# guest_room_controller_V2.net
KiCad netlist of a schematic drawn in EAGLE
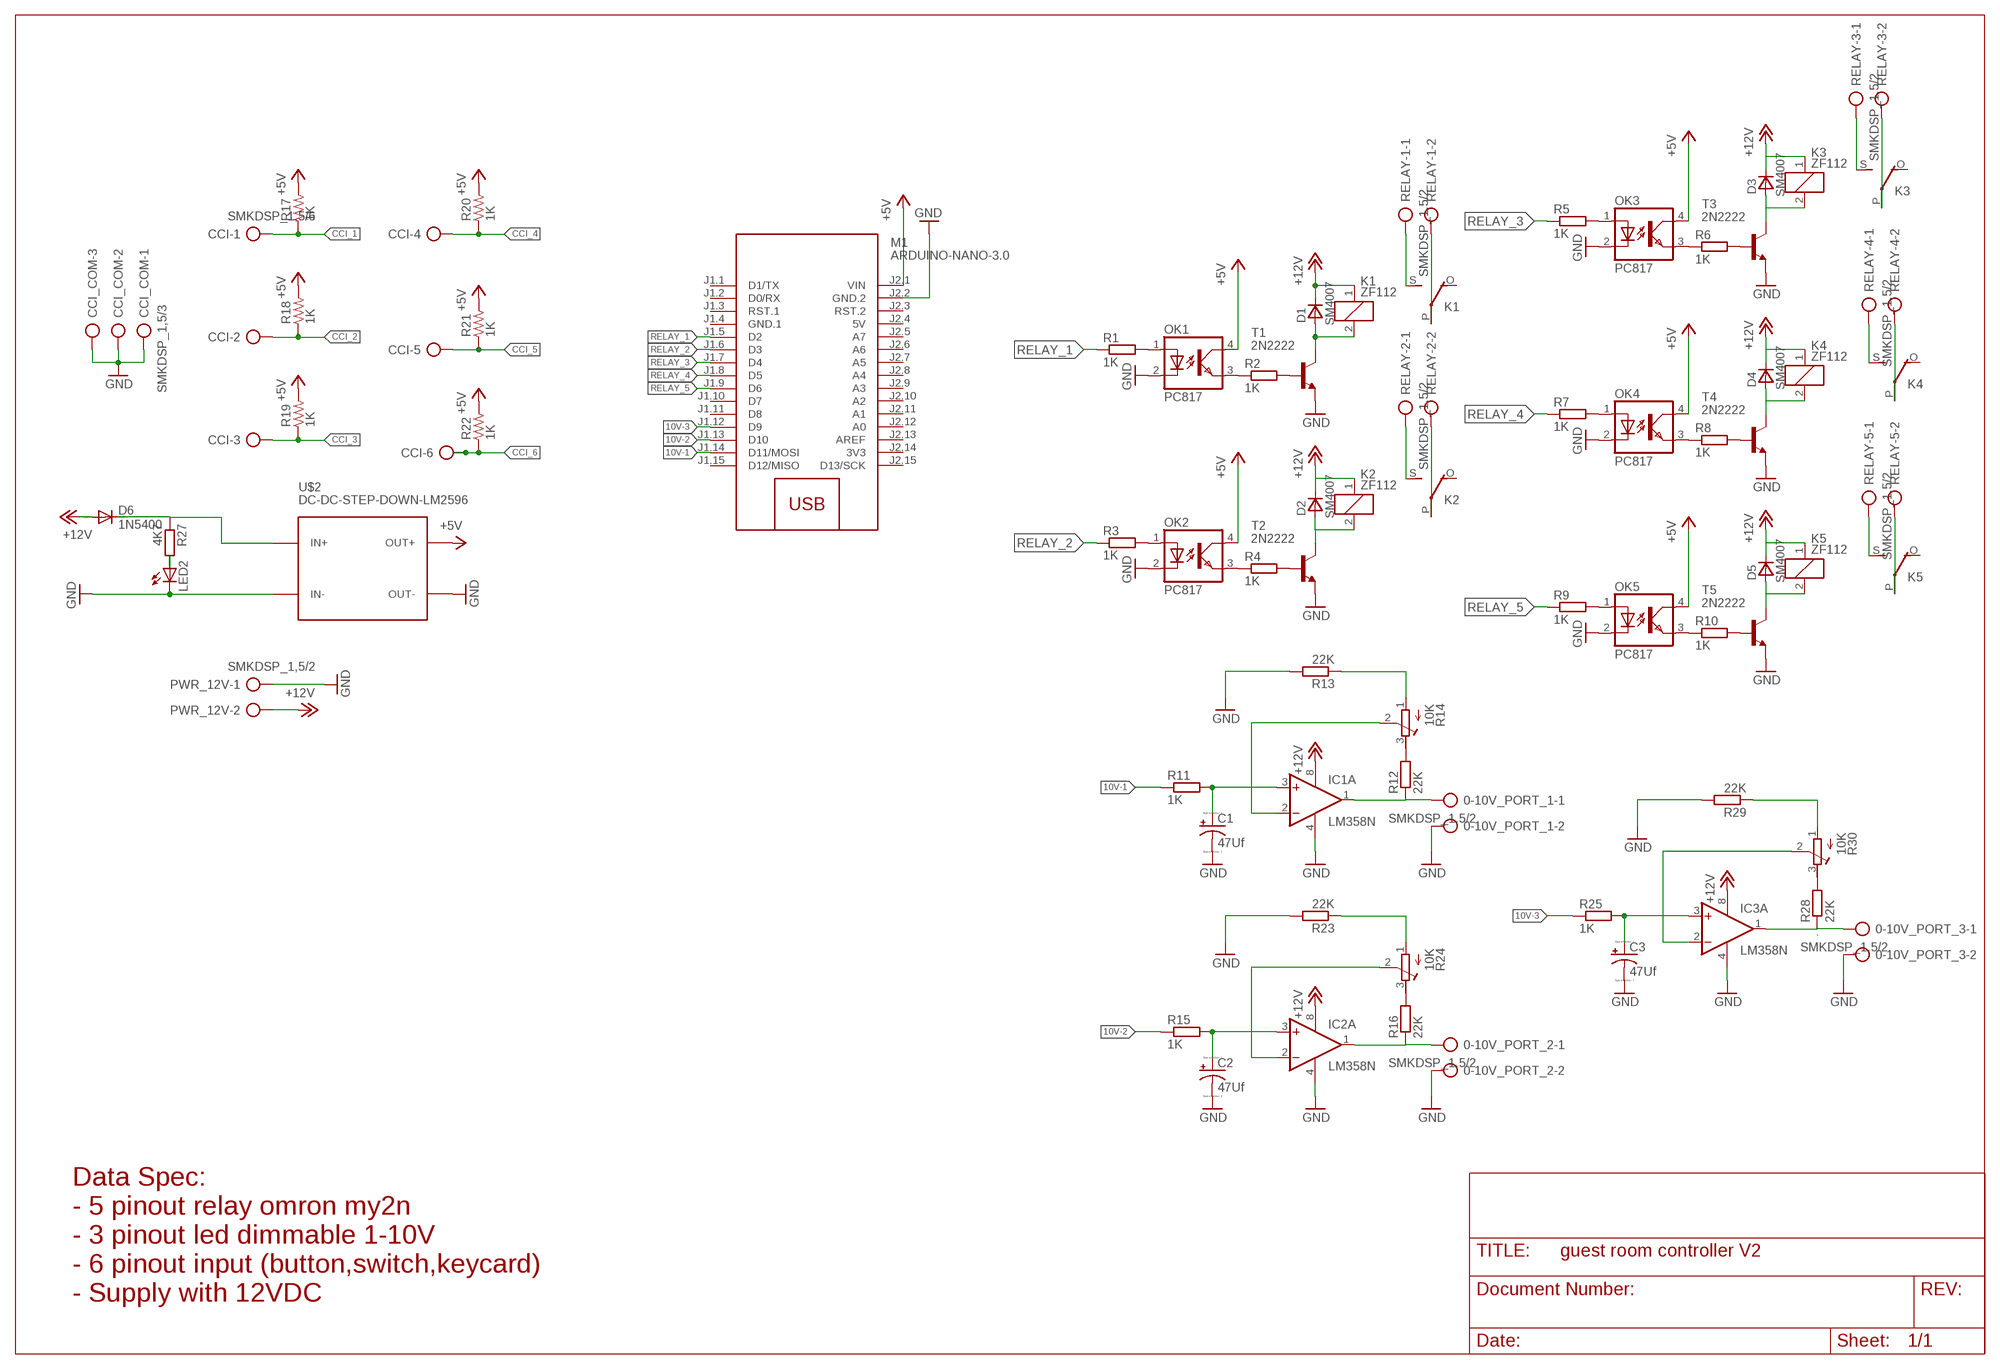
[diagram p0: schematic, sheet 1]

(export (version "E")
  (design (tool "Eeschema 10.0.6"))
  (components
    (comp (ref "0-10V_PORT_1")
      (value "SMKDSP_1,5/2")
      (footprint "eagle-import:SMKDSP_1,5_2")
      (fields (field (name "MF") "FARNELL") (field (name "MPN") "1733570"))
      (libsource (lib "eagle-import") (part "SMKDSP_1,5/2"))
    )
    (comp (ref "0-10V_PORT_2")
      (value "SMKDSP_1,5/2")
      (footprint "eagle-import:SMKDSP_1,5_2")
      (fields (field (name "MF") "FARNELL") (field (name "MPN") "1733570"))
      (libsource (lib "eagle-import") (part "SMKDSP_1,5/2"))
    )
    (comp (ref "0-10V_PORT_3")
      (value "SMKDSP_1,5/2")
      (footprint "eagle-import:SMKDSP_1,5_2")
      (fields (field (name "MF") "FARNELL") (field (name "MPN") "1733570"))
      (libsource (lib "eagle-import") (part "SMKDSP_1,5/2"))
    )
    (comp (ref "C1")
      (value "47Uf")
      (footprint "eagle-import:E2,5-6")
      (libsource (lib "eagle-import") (part "CPOL-USE2.5-6"))
    )
    (comp (ref "C2")
      (value "47Uf")
      (footprint "eagle-import:E2,5-6")
      (libsource (lib "eagle-import") (part "CPOL-USE2.5-6"))
    )
    (comp (ref "C3")
      (value "47Uf")
      (footprint "eagle-import:E2,5-6")
      (libsource (lib "eagle-import") (part "CPOL-USE2.5-6"))
    )
    (comp (ref "CCI")
      (value "SMKDSP_1,5/6")
      (footprint "eagle-import:SMKDSP_1,5_6")
      (fields (field (name "MF") "FARNELL") (field (name "MPN") "1733619"))
      (libsource (lib "eagle-import") (part "SMKDSP_1,5/6"))
    )
    (comp (ref "CCI_COM")
      (value "SMKDSP_1,5/3")
      (footprint "eagle-import:SMKDSP_1,5_3")
      (fields (field (name "MF") "FARNELL") (field (name "MPN") "1733583"))
      (libsource (lib "eagle-import") (part "SMKDSP_1,5/3"))
    )
    (comp (ref "D1")
      (value "SM4007")
      (footprint "eagle-import:MELF-MLL41")
      (libsource (lib "eagle-import") (part "SM4007"))
    )
    (comp (ref "D2")
      (value "SM4007")
      (footprint "eagle-import:MELF-MLL41")
      (libsource (lib "eagle-import") (part "SM4007"))
    )
    (comp (ref "D3")
      (value "SM4007")
      (footprint "eagle-import:MELF-MLL41")
      (libsource (lib "eagle-import") (part "SM4007"))
    )
    (comp (ref "D4")
      (value "SM4007")
      (footprint "eagle-import:MELF-MLL41")
      (libsource (lib "eagle-import") (part "SM4007"))
    )
    (comp (ref "D5")
      (value "SM4007")
      (footprint "eagle-import:MELF-MLL41")
      (libsource (lib "eagle-import") (part "SM4007"))
    )
    (comp (ref "D6")
      (value "1N5400")
      (footprint "eagle-import:DO201-15")
      (libsource (lib "eagle-import") (part "1N5400"))
    )
    (comp (ref "IC1")
      (value "LM358N")
      (footprint "eagle-import:DIL08")
      (libsource (lib "eagle-import") (part "LM358N"))
    )
    (comp (ref "IC2")
      (value "LM358N")
      (footprint "eagle-import:DIL08")
      (libsource (lib "eagle-import") (part "LM358N"))
    )
    (comp (ref "IC3")
      (value "LM358N")
      (footprint "eagle-import:DIL08")
      (libsource (lib "eagle-import") (part "LM358N"))
    )
    (comp (ref "K1")
      (value "ZF112")
      (footprint "eagle-import:ZF112")
      (libsource (lib "eagle-import") (part "ZF112"))
    )
    (comp (ref "K2")
      (value "ZF112")
      (footprint "eagle-import:ZF112")
      (libsource (lib "eagle-import") (part "ZF112"))
    )
    (comp (ref "K3")
      (value "ZF112")
      (footprint "eagle-import:ZF112")
      (libsource (lib "eagle-import") (part "ZF112"))
    )
    (comp (ref "K4")
      (value "ZF112")
      (footprint "eagle-import:ZF112")
      (libsource (lib "eagle-import") (part "ZF112"))
    )
    (comp (ref "K5")
      (value "ZF112")
      (footprint "eagle-import:ZF112")
      (libsource (lib "eagle-import") (part "ZF112"))
    )
    (comp (ref "LED2")
      (value "LED3MM")
      (footprint "eagle-import:LED3MM")
      (libsource (lib "eagle-import") (part "LED3MM"))
    )
    (comp (ref "M1")
      (value "ARDUINO-NANO-3.0")
      (footprint "eagle-import:ARDUINO-NANO-3.0")
      (libsource (lib "eagle-import") (part "ARDUINO-NANO-3.0"))
    )
    (comp (ref "OK1")
      (value "PC817")
      (footprint "eagle-import:DIL04")
      (fields (field (name "MPN") "PC817X4J000F"))
      (libsource (lib "eagle-import") (part "PC817"))
    )
    (comp (ref "OK2")
      (value "PC817")
      (footprint "eagle-import:DIL04")
      (fields (field (name "MPN") "PC817X4J000F"))
      (libsource (lib "eagle-import") (part "PC817"))
    )
    (comp (ref "OK3")
      (value "PC817")
      (footprint "eagle-import:DIL04")
      (fields (field (name "MPN") "PC817X4J000F"))
      (libsource (lib "eagle-import") (part "PC817"))
    )
    (comp (ref "OK4")
      (value "PC817")
      (footprint "eagle-import:DIL04")
      (fields (field (name "MPN") "PC817X4J000F"))
      (libsource (lib "eagle-import") (part "PC817"))
    )
    (comp (ref "OK5")
      (value "PC817")
      (footprint "eagle-import:DIL04")
      (fields (field (name "MPN") "PC817X4J000F"))
      (libsource (lib "eagle-import") (part "PC817"))
    )
    (comp (ref "PWR_12V")
      (value "SMKDSP_1,5/2")
      (footprint "eagle-import:SMKDSP_1,5_2")
      (fields (field (name "MF") "FARNELL") (field (name "MPN") "1733570"))
      (libsource (lib "eagle-import") (part "SMKDSP_1,5/2"))
    )
    (comp (ref "R1")
      (value "1K")
      (footprint "eagle-import:0207_10")
      (libsource (lib "eagle-import") (part "R-EU_0207/10"))
    )
    (comp (ref "R2")
      (value "1K")
      (footprint "eagle-import:0207_10")
      (libsource (lib "eagle-import") (part "R-EU_0207/10"))
    )
    (comp (ref "R3")
      (value "1K")
      (footprint "eagle-import:0207_10")
      (libsource (lib "eagle-import") (part "R-EU_0207/10"))
    )
    (comp (ref "R4")
      (value "1K")
      (footprint "eagle-import:0207_10")
      (libsource (lib "eagle-import") (part "R-EU_0207/10"))
    )
    (comp (ref "R5")
      (value "1K")
      (footprint "eagle-import:0207_10")
      (libsource (lib "eagle-import") (part "R-EU_0207/10"))
    )
    (comp (ref "R6")
      (value "1K")
      (footprint "eagle-import:0207_10")
      (libsource (lib "eagle-import") (part "R-EU_0207/10"))
    )
    (comp (ref "R7")
      (value "1K")
      (footprint "eagle-import:0207_10")
      (libsource (lib "eagle-import") (part "R-EU_0207/10"))
    )
    (comp (ref "R8")
      (value "1K")
      (footprint "eagle-import:0207_10")
      (libsource (lib "eagle-import") (part "R-EU_0207/10"))
    )
    (comp (ref "R9")
      (value "1K")
      (footprint "eagle-import:0207_10")
      (libsource (lib "eagle-import") (part "R-EU_0207/10"))
    )
    (comp (ref "R10")
      (value "1K")
      (footprint "eagle-import:0207_10")
      (libsource (lib "eagle-import") (part "R-EU_0207/10"))
    )
    (comp (ref "R11")
      (value "1K")
      (footprint "eagle-import:0207_10")
      (libsource (lib "eagle-import") (part "R-EU_0207/10"))
    )
    (comp (ref "R12")
      (value "22K")
      (footprint "eagle-import:0207_10")
      (libsource (lib "eagle-import") (part "R-EU_0207/10"))
    )
    (comp (ref "R13")
      (value "22K")
      (footprint "eagle-import:0207_10")
      (libsource (lib "eagle-import") (part "R-EU_0207/10"))
    )
    (comp (ref "R14")
      (value "10K")
      (footprint "eagle-import:RTRIM64P")
      (libsource (lib "eagle-import") (part "R-TRIMM64P"))
    )
    (comp (ref "R15")
      (value "1K")
      (footprint "eagle-import:0207_10")
      (libsource (lib "eagle-import") (part "R-EU_0207/10"))
    )
    (comp (ref "R16")
      (value "22K")
      (footprint "eagle-import:0207_10")
      (libsource (lib "eagle-import") (part "R-EU_0207/10"))
    )
    (comp (ref "R17")
      (value "1K")
      (footprint "eagle-import:R1206")
      (libsource (lib "eagle-import") (part "R_1206"))
    )
    (comp (ref "R18")
      (value "1K")
      (footprint "eagle-import:R1206")
      (libsource (lib "eagle-import") (part "R_1206"))
    )
    (comp (ref "R19")
      (value "1K")
      (footprint "eagle-import:R1206")
      (libsource (lib "eagle-import") (part "R_1206"))
    )
    (comp (ref "R20")
      (value "1K")
      (footprint "eagle-import:R1206")
      (libsource (lib "eagle-import") (part "R_1206"))
    )
    (comp (ref "R21")
      (value "1K")
      (footprint "eagle-import:R1206")
      (libsource (lib "eagle-import") (part "R_1206"))
    )
    (comp (ref "R22")
      (value "1K")
      (footprint "eagle-import:R1206")
      (libsource (lib "eagle-import") (part "R_1206"))
    )
    (comp (ref "R23")
      (value "22K")
      (footprint "eagle-import:0207_10")
      (libsource (lib "eagle-import") (part "R-EU_0207/10"))
    )
    (comp (ref "R24")
      (value "10K")
      (footprint "eagle-import:RTRIM64P")
      (libsource (lib "eagle-import") (part "R-TRIMM64P"))
    )
    (comp (ref "R25")
      (value "1K")
      (footprint "eagle-import:0207_10")
      (libsource (lib "eagle-import") (part "R-EU_0207/10"))
    )
    (comp (ref "R27")
      (value "4K7")
      (footprint "eagle-import:0207_10")
      (libsource (lib "eagle-import") (part "R-EU_0207/10"))
    )
    (comp (ref "R28")
      (value "22K")
      (footprint "eagle-import:0207_10")
      (libsource (lib "eagle-import") (part "R-EU_0207/10"))
    )
    (comp (ref "R29")
      (value "22K")
      (footprint "eagle-import:0207_10")
      (libsource (lib "eagle-import") (part "R-EU_0207/10"))
    )
    (comp (ref "R30")
      (value "10K")
      (footprint "eagle-import:RTRIM64P")
      (libsource (lib "eagle-import") (part "R-TRIMM64P"))
    )
    (comp (ref "RELAY-1")
      (value "SMKDSP_1,5/2")
      (footprint "eagle-import:SMKDSP_1,5_2")
      (fields (field (name "MF") "FARNELL") (field (name "MPN") "1733570"))
      (libsource (lib "eagle-import") (part "SMKDSP_1,5/2"))
    )
    (comp (ref "RELAY-2")
      (value "SMKDSP_1,5/2")
      (footprint "eagle-import:SMKDSP_1,5_2")
      (fields (field (name "MF") "FARNELL") (field (name "MPN") "1733570"))
      (libsource (lib "eagle-import") (part "SMKDSP_1,5/2"))
    )
    (comp (ref "RELAY-3")
      (value "SMKDSP_1,5/2")
      (footprint "eagle-import:SMKDSP_1,5_2")
      (fields (field (name "MF") "FARNELL") (field (name "MPN") "1733570"))
      (libsource (lib "eagle-import") (part "SMKDSP_1,5/2"))
    )
    (comp (ref "RELAY-4")
      (value "SMKDSP_1,5/2")
      (footprint "eagle-import:SMKDSP_1,5_2")
      (fields (field (name "MF") "FARNELL") (field (name "MPN") "1733570"))
      (libsource (lib "eagle-import") (part "SMKDSP_1,5/2"))
    )
    (comp (ref "RELAY-5")
      (value "SMKDSP_1,5/2")
      (footprint "eagle-import:SMKDSP_1,5_2")
      (fields (field (name "MF") "FARNELL") (field (name "MPN") "1733570"))
      (libsource (lib "eagle-import") (part "SMKDSP_1,5/2"))
    )
    (comp (ref "T1")
      (value "2N2222")
      (footprint "eagle-import:TO18")
      (libsource (lib "eagle-import") (part "2N2222"))
    )
    (comp (ref "T2")
      (value "2N2222")
      (footprint "eagle-import:TO18")
      (libsource (lib "eagle-import") (part "2N2222"))
    )
    (comp (ref "T3")
      (value "2N2222")
      (footprint "eagle-import:TO18")
      (libsource (lib "eagle-import") (part "2N2222"))
    )
    (comp (ref "T4")
      (value "2N2222")
      (footprint "eagle-import:TO18")
      (libsource (lib "eagle-import") (part "2N2222"))
    )
    (comp (ref "T5")
      (value "2N2222")
      (footprint "eagle-import:TO18")
      (libsource (lib "eagle-import") (part "2N2222"))
    )
    (comp (ref "U$2")
      (value "DC-DC-STEP-DOWN-LM2596")
      (footprint "eagle-import:DC-DC-STEP-DOWN-LM2596")
      (libsource (lib "eagle-import") (part "DC-DC-STEP-DOWN-LM2596"))
    )
  )
  (nets
    (net (code "1") (name "+5V") (class "Default")
      (node (ref "M1") (pin "J2.1") (pinfunction "VIN_J2.1") (pintype "power_in"))
      (node (ref "OK1") (pin "4") (pinfunction "COL_4") (pintype "passive"))
      (node (ref "OK2") (pin "4") (pinfunction "COL_4") (pintype "passive"))
      (node (ref "OK3") (pin "4") (pinfunction "COL_4") (pintype "passive"))
      (node (ref "OK4") (pin "4") (pinfunction "COL_4") (pintype "passive"))
      (node (ref "OK5") (pin "4") (pinfunction "COL_4") (pintype "passive"))
      (node (ref "R17") (pin "2") (pinfunction "2_2") (pintype "passive"))
      (node (ref "R18") (pin "2") (pinfunction "2_2") (pintype "passive"))
      (node (ref "R19") (pin "2") (pinfunction "2_2") (pintype "passive"))
      (node (ref "R20") (pin "2") (pinfunction "2_2") (pintype "passive"))
      (node (ref "R21") (pin "2") (pinfunction "2_2") (pintype "passive"))
      (node (ref "R22") (pin "2") (pinfunction "2_2") (pintype "passive"))
      (node (ref "U$2") (pin "OUT+") (pinfunction "OUT+_OUT+") (pintype "bidirectional"))
    )
    (net (code "2") (name "+12V") (class "Default")
      (node (ref "D1") (pin "C") (pinfunction "C_C") (pintype "passive"))
      (node (ref "D2") (pin "C") (pinfunction "C_C") (pintype "passive"))
      (node (ref "D3") (pin "C") (pinfunction "C_C") (pintype "passive"))
      (node (ref "D4") (pin "C") (pinfunction "C_C") (pintype "passive"))
      (node (ref "D5") (pin "C") (pinfunction "C_C") (pintype "passive"))
      (node (ref "D6") (pin "A") (pinfunction "A_A") (pintype "passive"))
      (node (ref "IC1") (pin "8") (pinfunction "V+_8") (pintype "power_in"))
      (node (ref "IC2") (pin "8") (pinfunction "V+_8") (pintype "power_in"))
      (node (ref "IC3") (pin "8") (pinfunction "V+_8") (pintype "power_in"))
      (node (ref "K1") (pin "1") (pinfunction "1_1") (pintype "passive"))
      (node (ref "K2") (pin "1") (pinfunction "1_1") (pintype "passive"))
      (node (ref "K3") (pin "1") (pinfunction "1_1") (pintype "passive"))
      (node (ref "K4") (pin "1") (pinfunction "1_1") (pintype "passive"))
      (node (ref "K5") (pin "1") (pinfunction "1_1") (pintype "passive"))
      (node (ref "PWR_12V") (pin "2") (pinfunction "KL_2") (pintype "passive"))
    )
    (net (code "3") (name "/3V3") (class "Default")
      (node (ref "M1") (pin "J2.14") (pinfunction "3V3_J2.14") (pintype "power_in"))
    )
    (net (code "4") (name "/5V") (class "Default")
      (node (ref "M1") (pin "J2.4") (pinfunction "5V_J2.4") (pintype "power_in"))
    )
    (net (code "5") (name "/GND.1") (class "Default")
      (node (ref "M1") (pin "J1.4") (pinfunction "GND.1_J1.4") (pintype "power_in"))
    )
    (net (code "6") (name "10V-1") (class "Default")
      (node (ref "M1") (pin "J1.14") (pinfunction "D11/MOSI_J1.14") (pintype "bidirectional"))
      (node (ref "R11") (pin "1") (pinfunction "1_1") (pintype "passive"))
    )
    (net (code "7") (name "10V-2") (class "Default")
      (node (ref "M1") (pin "J1.13") (pinfunction "D10_J1.13") (pintype "bidirectional"))
      (node (ref "R15") (pin "1") (pinfunction "1_1") (pintype "passive"))
    )
    (net (code "8") (name "10V-3") (class "Default")
      (node (ref "M1") (pin "J1.12") (pinfunction "D9_J1.12") (pintype "bidirectional"))
      (node (ref "R25") (pin "1") (pinfunction "1_1") (pintype "passive"))
    )
    (net (code "9") (name "CCI_1") (class "Default")
      (node (ref "CCI") (pin "1") (pinfunction "KL_1") (pintype "passive"))
      (node (ref "R17") (pin "1") (pinfunction "1_1") (pintype "passive"))
    )
    (net (code "10") (name "CCI_2") (class "Default")
      (node (ref "CCI") (pin "2") (pinfunction "KL_2") (pintype "passive"))
      (node (ref "R18") (pin "1") (pinfunction "1_1") (pintype "passive"))
    )
    (net (code "11") (name "CCI_3") (class "Default")
      (node (ref "CCI") (pin "3") (pinfunction "KL_3") (pintype "passive"))
      (node (ref "R19") (pin "1") (pinfunction "1_1") (pintype "passive"))
    )
    (net (code "12") (name "CCI_4") (class "Default")
      (node (ref "CCI") (pin "4") (pinfunction "KL_4") (pintype "passive"))
      (node (ref "R20") (pin "1") (pinfunction "1_1") (pintype "passive"))
    )
    (net (code "13") (name "CCI_5") (class "Default")
      (node (ref "CCI") (pin "5") (pinfunction "KL_5") (pintype "passive"))
      (node (ref "R21") (pin "1") (pinfunction "1_1") (pintype "passive"))
    )
    (net (code "14") (name "CCI_6") (class "Default")
      (node (ref "CCI") (pin "6") (pinfunction "KL_6") (pintype "passive"))
      (node (ref "R22") (pin "1") (pinfunction "1_1") (pintype "passive"))
    )
    (net (code "15") (name "GND") (class "Default")
      (node (ref "0-10V_PORT_1") (pin "2") (pinfunction "KL_2") (pintype "passive"))
      (node (ref "0-10V_PORT_2") (pin "2") (pinfunction "KL_2") (pintype "passive"))
      (node (ref "0-10V_PORT_3") (pin "2") (pinfunction "KL_2") (pintype "passive"))
      (node (ref "C1") (pin "-") (pinfunction "-_-") (pintype "passive"))
      (node (ref "C2") (pin "-") (pinfunction "-_-") (pintype "passive"))
      (node (ref "C3") (pin "-") (pinfunction "-_-") (pintype "passive"))
      (node (ref "CCI_COM") (pin "1") (pinfunction "KL_1") (pintype "passive"))
      (node (ref "CCI_COM") (pin "2") (pinfunction "KL_2") (pintype "passive"))
      (node (ref "CCI_COM") (pin "3") (pinfunction "KL_3") (pintype "passive"))
      (node (ref "IC1") (pin "4") (pinfunction "V-_4") (pintype "power_in"))
      (node (ref "IC2") (pin "4") (pinfunction "V-_4") (pintype "power_in"))
      (node (ref "IC3") (pin "4") (pinfunction "V-_4") (pintype "power_in"))
      (node (ref "LED2") (pin "K") (pinfunction "C_K") (pintype "passive"))
      (node (ref "M1") (pin "J2.2") (pinfunction "GND.2_J2.2") (pintype "power_in"))
      (node (ref "OK1") (pin "2") (pinfunction "C_2") (pintype "passive"))
      (node (ref "OK2") (pin "2") (pinfunction "C_2") (pintype "passive"))
      (node (ref "OK3") (pin "2") (pinfunction "C_2") (pintype "passive"))
      (node (ref "OK4") (pin "2") (pinfunction "C_2") (pintype "passive"))
      (node (ref "OK5") (pin "2") (pinfunction "C_2") (pintype "passive"))
      (node (ref "PWR_12V") (pin "1") (pinfunction "KL_1") (pintype "passive"))
      (node (ref "R13") (pin "2") (pinfunction "2_2") (pintype "passive"))
      (node (ref "R23") (pin "2") (pinfunction "2_2") (pintype "passive"))
      (node (ref "R29") (pin "2") (pinfunction "2_2") (pintype "passive"))
      (node (ref "T1") (pin "1") (pinfunction "E_1") (pintype "passive"))
      (node (ref "T2") (pin "1") (pinfunction "E_1") (pintype "passive"))
      (node (ref "T3") (pin "1") (pinfunction "E_1") (pintype "passive"))
      (node (ref "T4") (pin "1") (pinfunction "E_1") (pintype "passive"))
      (node (ref "T5") (pin "1") (pinfunction "E_1") (pintype "passive"))
      (node (ref "U$2") (pin "IN-") (pinfunction "IN-_IN-") (pintype "bidirectional"))
      (node (ref "U$2") (pin "OUT-") (pinfunction "OUT-_OUT-") (pintype "bidirectional"))
    )
    (net (code "16") (name "Net-(0-10V_PORT_1A-KL)") (class "Default")
      (node (ref "0-10V_PORT_1") (pin "1") (pinfunction "KL_1") (pintype "passive"))
      (node (ref "IC1") (pin "1") (pinfunction "OUT_1") (pintype "output"))
      (node (ref "R12") (pin "1") (pinfunction "1_1") (pintype "passive"))
    )
    (net (code "17") (name "Net-(0-10V_PORT_2A-KL)") (class "Default")
      (node (ref "0-10V_PORT_2") (pin "1") (pinfunction "KL_1") (pintype "passive"))
      (node (ref "IC2") (pin "1") (pinfunction "OUT_1") (pintype "output"))
      (node (ref "R16") (pin "1") (pinfunction "1_1") (pintype "passive"))
    )
    (net (code "18") (name "Net-(0-10V_PORT_3A-KL)") (class "Default")
      (node (ref "0-10V_PORT_3") (pin "1") (pinfunction "KL_1") (pintype "passive"))
      (node (ref "IC3") (pin "1") (pinfunction "OUT_1") (pintype "output"))
      (node (ref "R28") (pin "1") (pinfunction "1_1") (pintype "passive"))
    )
    (net (code "19") (name "Net-(D6-PadC)") (class "Default")
      (node (ref "D6") (pin "C") (pinfunction "C_C") (pintype "passive"))
      (node (ref "R27") (pin "1") (pinfunction "1_1") (pintype "passive"))
      (node (ref "U$2") (pin "IN+") (pinfunction "IN+_IN+") (pintype "bidirectional"))
    )
    (net (code "20") (name "Net-(IC1A-+IN)") (class "Default")
      (node (ref "C1") (pin "+") (pinfunction "+_+") (pintype "passive"))
      (node (ref "IC1") (pin "3") (pinfunction "+IN_3") (pintype "input"))
      (node (ref "R11") (pin "2") (pinfunction "2_2") (pintype "passive"))
    )
    (net (code "21") (name "Net-(IC1A--IN)") (class "Default")
      (node (ref "IC1") (pin "2") (pinfunction "-IN_2") (pintype "input"))
      (node (ref "R14") (pin "2") (pinfunction "S_2") (pintype "passive"))
    )
    (net (code "22") (name "Net-(IC2A-+IN)") (class "Default")
      (node (ref "C2") (pin "+") (pinfunction "+_+") (pintype "passive"))
      (node (ref "IC2") (pin "3") (pinfunction "+IN_3") (pintype "input"))
      (node (ref "R15") (pin "2") (pinfunction "2_2") (pintype "passive"))
    )
    (net (code "23") (name "Net-(IC2A--IN)") (class "Default")
      (node (ref "IC2") (pin "2") (pinfunction "-IN_2") (pintype "input"))
      (node (ref "R24") (pin "2") (pinfunction "S_2") (pintype "passive"))
    )
    (net (code "24") (name "Net-(IC3A-+IN)") (class "Default")
      (node (ref "C3") (pin "+") (pinfunction "+_+") (pintype "passive"))
      (node (ref "IC3") (pin "3") (pinfunction "+IN_3") (pintype "input"))
      (node (ref "R25") (pin "2") (pinfunction "2_2") (pintype "passive"))
    )
    (net (code "25") (name "Net-(IC3A--IN)") (class "Default")
      (node (ref "IC3") (pin "2") (pinfunction "-IN_2") (pintype "input"))
      (node (ref "R30") (pin "2") (pinfunction "S_2") (pintype "passive"))
    )
    (net (code "26") (name "Net-(LED2-PadA)") (class "Default")
      (node (ref "LED2") (pin "A") (pinfunction "A_A") (pintype "passive"))
      (node (ref "R27") (pin "2") (pinfunction "2_2") (pintype "passive"))
    )
    (net (code "27") (name "Net-(OK1-A)") (class "Default")
      (node (ref "OK1") (pin "1") (pinfunction "A_1") (pintype "passive"))
      (node (ref "R1") (pin "2") (pinfunction "2_2") (pintype "passive"))
    )
    (net (code "28") (name "Net-(OK1-EMIT)") (class "Default")
      (node (ref "OK1") (pin "3") (pinfunction "EMIT_3") (pintype "passive"))
      (node (ref "R2") (pin "1") (pinfunction "1_1") (pintype "passive"))
    )
    (net (code "29") (name "Net-(OK2-A)") (class "Default")
      (node (ref "OK2") (pin "1") (pinfunction "A_1") (pintype "passive"))
      (node (ref "R3") (pin "2") (pinfunction "2_2") (pintype "passive"))
    )
    (net (code "30") (name "Net-(OK2-EMIT)") (class "Default")
      (node (ref "OK2") (pin "3") (pinfunction "EMIT_3") (pintype "passive"))
      (node (ref "R4") (pin "1") (pinfunction "1_1") (pintype "passive"))
    )
    (net (code "31") (name "Net-(OK3-A)") (class "Default")
      (node (ref "OK3") (pin "1") (pinfunction "A_1") (pintype "passive"))
      (node (ref "R5") (pin "2") (pinfunction "2_2") (pintype "passive"))
    )
    (net (code "32") (name "Net-(OK3-EMIT)") (class "Default")
      (node (ref "OK3") (pin "3") (pinfunction "EMIT_3") (pintype "passive"))
      (node (ref "R6") (pin "1") (pinfunction "1_1") (pintype "passive"))
    )
    (net (code "33") (name "Net-(OK4-A)") (class "Default")
      (node (ref "OK4") (pin "1") (pinfunction "A_1") (pintype "passive"))
      (node (ref "R7") (pin "2") (pinfunction "2_2") (pintype "passive"))
    )
    (net (code "34") (name "Net-(OK4-EMIT)") (class "Default")
      (node (ref "OK4") (pin "3") (pinfunction "EMIT_3") (pintype "passive"))
      (node (ref "R8") (pin "1") (pinfunction "1_1") (pintype "passive"))
    )
    (net (code "35") (name "Net-(OK5-A)") (class "Default")
      (node (ref "OK5") (pin "1") (pinfunction "A_1") (pintype "passive"))
      (node (ref "R9") (pin "2") (pinfunction "2_2") (pintype "passive"))
    )
    (net (code "36") (name "Net-(OK5-EMIT)") (class "Default")
      (node (ref "OK5") (pin "3") (pinfunction "EMIT_3") (pintype "passive"))
      (node (ref "R10") (pin "1") (pinfunction "1_1") (pintype "passive"))
    )
    (net (code "37") (name "Net-(R14-A)") (class "Default")
      (node (ref "R13") (pin "1") (pinfunction "1_1") (pintype "passive"))
      (node (ref "R14") (pin "1") (pinfunction "A_1") (pintype "passive"))
    )
    (net (code "38") (name "Net-(R14-E)") (class "Default")
      (node (ref "R12") (pin "2") (pinfunction "2_2") (pintype "passive"))
      (node (ref "R14") (pin "3") (pinfunction "E_3") (pintype "passive"))
    )
    (net (code "39") (name "Net-(R24-A)") (class "Default")
      (node (ref "R23") (pin "1") (pinfunction "1_1") (pintype "passive"))
      (node (ref "R24") (pin "1") (pinfunction "A_1") (pintype "passive"))
    )
    (net (code "40") (name "Net-(R24-E)") (class "Default")
      (node (ref "R16") (pin "2") (pinfunction "2_2") (pintype "passive"))
      (node (ref "R24") (pin "3") (pinfunction "E_3") (pintype "passive"))
    )
    (net (code "41") (name "Net-(R30-A)") (class "Default")
      (node (ref "R29") (pin "1") (pinfunction "1_1") (pintype "passive"))
      (node (ref "R30") (pin "1") (pinfunction "A_1") (pintype "passive"))
    )
    (net (code "42") (name "Net-(R30-E)") (class "Default")
      (node (ref "R28") (pin "2") (pinfunction "2_2") (pintype "passive"))
      (node (ref "R30") (pin "3") (pinfunction "E_3") (pintype "passive"))
    )
    (net (code "43") (name "Net-(RELAY-1A-KL)") (class "Default")
      (node (ref "K1") (pin "S") (pinfunction "S_S") (pintype "passive"))
      (node (ref "RELAY-1") (pin "1") (pinfunction "KL_1") (pintype "passive"))
    )
    (net (code "44") (name "Net-(RELAY-1B-KL)") (class "Default")
      (node (ref "K1") (pin "P") (pinfunction "P_P") (pintype "passive"))
      (node (ref "RELAY-1") (pin "2") (pinfunction "KL_2") (pintype "passive"))
    )
    (net (code "45") (name "Net-(RELAY-2A-KL)") (class "Default")
      (node (ref "K2") (pin "S") (pinfunction "S_S") (pintype "passive"))
      (node (ref "RELAY-2") (pin "1") (pinfunction "KL_1") (pintype "passive"))
    )
    (net (code "46") (name "Net-(RELAY-2B-KL)") (class "Default")
      (node (ref "K2") (pin "P") (pinfunction "P_P") (pintype "passive"))
      (node (ref "RELAY-2") (pin "2") (pinfunction "KL_2") (pintype "passive"))
    )
    (net (code "47") (name "Net-(RELAY-3A-KL)") (class "Default")
      (node (ref "K3") (pin "S") (pinfunction "S_S") (pintype "passive"))
      (node (ref "RELAY-3") (pin "1") (pinfunction "KL_1") (pintype "passive"))
    )
    (net (code "48") (name "Net-(RELAY-3B-KL)") (class "Default")
      (node (ref "K3") (pin "P") (pinfunction "P_P") (pintype "passive"))
      (node (ref "RELAY-3") (pin "2") (pinfunction "KL_2") (pintype "passive"))
    )
    (net (code "49") (name "Net-(RELAY-4A-KL)") (class "Default")
      (node (ref "K4") (pin "S") (pinfunction "S_S") (pintype "passive"))
      (node (ref "RELAY-4") (pin "1") (pinfunction "KL_1") (pintype "passive"))
    )
    (net (code "50") (name "Net-(RELAY-4B-KL)") (class "Default")
      (node (ref "K4") (pin "P") (pinfunction "P_P") (pintype "passive"))
      (node (ref "RELAY-4") (pin "2") (pinfunction "KL_2") (pintype "passive"))
    )
    (net (code "51") (name "Net-(RELAY-5A-KL)") (class "Default")
      (node (ref "K5") (pin "S") (pinfunction "S_S") (pintype "passive"))
      (node (ref "RELAY-5") (pin "1") (pinfunction "KL_1") (pintype "passive"))
    )
    (net (code "52") (name "Net-(RELAY-5B-KL)") (class "Default")
      (node (ref "K5") (pin "P") (pinfunction "P_P") (pintype "passive"))
      (node (ref "RELAY-5") (pin "2") (pinfunction "KL_2") (pintype "passive"))
    )
    (net (code "53") (name "Net-(T1-B)") (class "Default")
      (node (ref "R2") (pin "2") (pinfunction "2_2") (pintype "passive"))
      (node (ref "T1") (pin "2") (pinfunction "B_2") (pintype "passive"))
    )
    (net (code "54") (name "Net-(T1-C)") (class "Default")
      (node (ref "D1") (pin "A") (pinfunction "A_A") (pintype "passive"))
      (node (ref "K1") (pin "2") (pinfunction "2_2") (pintype "passive"))
      (node (ref "T1") (pin "3") (pinfunction "C_3") (pintype "passive"))
    )
    (net (code "55") (name "Net-(T2-B)") (class "Default")
      (node (ref "R4") (pin "2") (pinfunction "2_2") (pintype "passive"))
      (node (ref "T2") (pin "2") (pinfunction "B_2") (pintype "passive"))
    )
    (net (code "56") (name "Net-(T2-C)") (class "Default")
      (node (ref "D2") (pin "A") (pinfunction "A_A") (pintype "passive"))
      (node (ref "K2") (pin "2") (pinfunction "2_2") (pintype "passive"))
      (node (ref "T2") (pin "3") (pinfunction "C_3") (pintype "passive"))
    )
    (net (code "57") (name "Net-(T3-B)") (class "Default")
      (node (ref "R6") (pin "2") (pinfunction "2_2") (pintype "passive"))
      (node (ref "T3") (pin "2") (pinfunction "B_2") (pintype "passive"))
    )
    (net (code "58") (name "Net-(T3-C)") (class "Default")
      (node (ref "D3") (pin "A") (pinfunction "A_A") (pintype "passive"))
      (node (ref "K3") (pin "2") (pinfunction "2_2") (pintype "passive"))
      (node (ref "T3") (pin "3") (pinfunction "C_3") (pintype "passive"))
    )
    (net (code "59") (name "Net-(T4-B)") (class "Default")
      (node (ref "R8") (pin "2") (pinfunction "2_2") (pintype "passive"))
      (node (ref "T4") (pin "2") (pinfunction "B_2") (pintype "passive"))
    )
    (net (code "60") (name "Net-(T4-C)") (class "Default")
      (node (ref "D4") (pin "A") (pinfunction "A_A") (pintype "passive"))
      (node (ref "K4") (pin "2") (pinfunction "2_2") (pintype "passive"))
      (node (ref "T4") (pin "3") (pinfunction "C_3") (pintype "passive"))
    )
    (net (code "61") (name "Net-(T5-B)") (class "Default")
      (node (ref "R10") (pin "2") (pinfunction "2_2") (pintype "passive"))
      (node (ref "T5") (pin "2") (pinfunction "B_2") (pintype "passive"))
    )
    (net (code "62") (name "Net-(T5-C)") (class "Default")
      (node (ref "D5") (pin "A") (pinfunction "A_A") (pintype "passive"))
      (node (ref "K5") (pin "2") (pinfunction "2_2") (pintype "passive"))
      (node (ref "T5") (pin "3") (pinfunction "C_3") (pintype "passive"))
    )
    (net (code "63") (name "RELAY_1") (class "Default")
      (node (ref "M1") (pin "J1.5") (pinfunction "D2_J1.5") (pintype "bidirectional"))
      (node (ref "R1") (pin "1") (pinfunction "1_1") (pintype "passive"))
    )
    (net (code "64") (name "RELAY_2") (class "Default")
      (node (ref "M1") (pin "J1.6") (pinfunction "D3_J1.6") (pintype "bidirectional"))
      (node (ref "R3") (pin "1") (pinfunction "1_1") (pintype "passive"))
    )
    (net (code "65") (name "RELAY_3") (class "Default")
      (node (ref "M1") (pin "J1.7") (pinfunction "D4_J1.7") (pintype "bidirectional"))
      (node (ref "R5") (pin "1") (pinfunction "1_1") (pintype "passive"))
    )
    (net (code "66") (name "RELAY_4") (class "Default")
      (node (ref "M1") (pin "J1.8") (pinfunction "D5_J1.8") (pintype "bidirectional"))
      (node (ref "R7") (pin "1") (pinfunction "1_1") (pintype "passive"))
    )
    (net (code "67") (name "RELAY_5") (class "Default")
      (node (ref "M1") (pin "J1.9") (pinfunction "D6_J1.9") (pintype "bidirectional"))
      (node (ref "R9") (pin "1") (pinfunction "1_1") (pintype "passive"))
    )
    (net (code "68") (name "unconnected-(K1-PadO)") (class "Default")
      (node (ref "K1") (pin "O") (pinfunction "O_O") (pintype "passive"))
    )
    (net (code "69") (name "unconnected-(K2-PadO)") (class "Default")
      (node (ref "K2") (pin "O") (pinfunction "O_O") (pintype "passive"))
    )
    (net (code "70") (name "unconnected-(K3-PadO)") (class "Default")
      (node (ref "K3") (pin "O") (pinfunction "O_O") (pintype "passive"))
    )
    (net (code "71") (name "unconnected-(K4-PadO)") (class "Default")
      (node (ref "K4") (pin "O") (pinfunction "O_O") (pintype "passive"))
    )
    (net (code "72") (name "unconnected-(K5-PadO)") (class "Default")
      (node (ref "K5") (pin "O") (pinfunction "O_O") (pintype "passive"))
    )
    (net (code "73") (name "unconnected-(M1-A0-PadJ2.12)") (class "Default")
      (node (ref "M1") (pin "J2.12") (pinfunction "A0_J2.12") (pintype "bidirectional"))
    )
    (net (code "74") (name "unconnected-(M1-A1-PadJ2.11)") (class "Default")
      (node (ref "M1") (pin "J2.11") (pinfunction "A1_J2.11") (pintype "bidirectional"))
    )
    (net (code "75") (name "unconnected-(M1-A2-PadJ2.10)") (class "Default")
      (node (ref "M1") (pin "J2.10") (pinfunction "A2_J2.10") (pintype "bidirectional"))
    )
    (net (code "76") (name "unconnected-(M1-A3-PadJ2.9)") (class "Default")
      (node (ref "M1") (pin "J2.9") (pinfunction "A3_J2.9") (pintype "bidirectional"))
    )
    (net (code "77") (name "unconnected-(M1-A4-PadJ2.8)") (class "Default")
      (node (ref "M1") (pin "J2.8") (pinfunction "A4_J2.8") (pintype "bidirectional"))
    )
    (net (code "78") (name "unconnected-(M1-A5-PadJ2.7)") (class "Default")
      (node (ref "M1") (pin "J2.7") (pinfunction "A5_J2.7") (pintype "bidirectional"))
    )
    (net (code "79") (name "unconnected-(M1-A6-PadJ2.6)") (class "Default")
      (node (ref "M1") (pin "J2.6") (pinfunction "A6_J2.6") (pintype "bidirectional"))
    )
    (net (code "80") (name "unconnected-(M1-A7-PadJ2.5)") (class "Default")
      (node (ref "M1") (pin "J2.5") (pinfunction "A7_J2.5") (pintype "bidirectional"))
    )
    (net (code "81") (name "unconnected-(M1-AREF-PadJ2.13)") (class "Default")
      (node (ref "M1") (pin "J2.13") (pinfunction "AREF_J2.13") (pintype "bidirectional"))
    )
    (net (code "82") (name "unconnected-(M1-D0{slash}RX-PadJ1.2)") (class "Default")
      (node (ref "M1") (pin "J1.2") (pinfunction "D0/RX_J1.2") (pintype "bidirectional"))
    )
    (net (code "83") (name "unconnected-(M1-D1{slash}TX-PadJ1.1)") (class "Default")
      (node (ref "M1") (pin "J1.1") (pinfunction "D1/TX_J1.1") (pintype "bidirectional"))
    )
    (net (code "84") (name "unconnected-(M1-D7-PadJ1.10)") (class "Default")
      (node (ref "M1") (pin "J1.10") (pinfunction "D7_J1.10") (pintype "bidirectional"))
    )
    (net (code "85") (name "unconnected-(M1-D8-PadJ1.11)") (class "Default")
      (node (ref "M1") (pin "J1.11") (pinfunction "D8_J1.11") (pintype "bidirectional"))
    )
    (net (code "86") (name "unconnected-(M1-D12{slash}MISO-PadJ1.15)") (class "Default")
      (node (ref "M1") (pin "J1.15") (pinfunction "D12/MISO_J1.15") (pintype "bidirectional"))
    )
    (net (code "87") (name "unconnected-(M1-D13{slash}SCK-PadJ2.15)") (class "Default")
      (node (ref "M1") (pin "J2.15") (pinfunction "D13/SCK_J2.15") (pintype "bidirectional"))
    )
    (net (code "88") (name "unconnected-(M1-RST.1-PadJ1.3)") (class "Default")
      (node (ref "M1") (pin "J1.3") (pinfunction "RST.1_J1.3") (pintype "bidirectional"))
    )
    (net (code "89") (name "unconnected-(M1-RST.2-PadJ2.3)") (class "Default")
      (node (ref "M1") (pin "J2.3") (pinfunction "RST.2_J2.3") (pintype "bidirectional"))
    )
  )
)
